# AAA_third_source.net
KiCad netlist of a schematic drawn in EAGLE
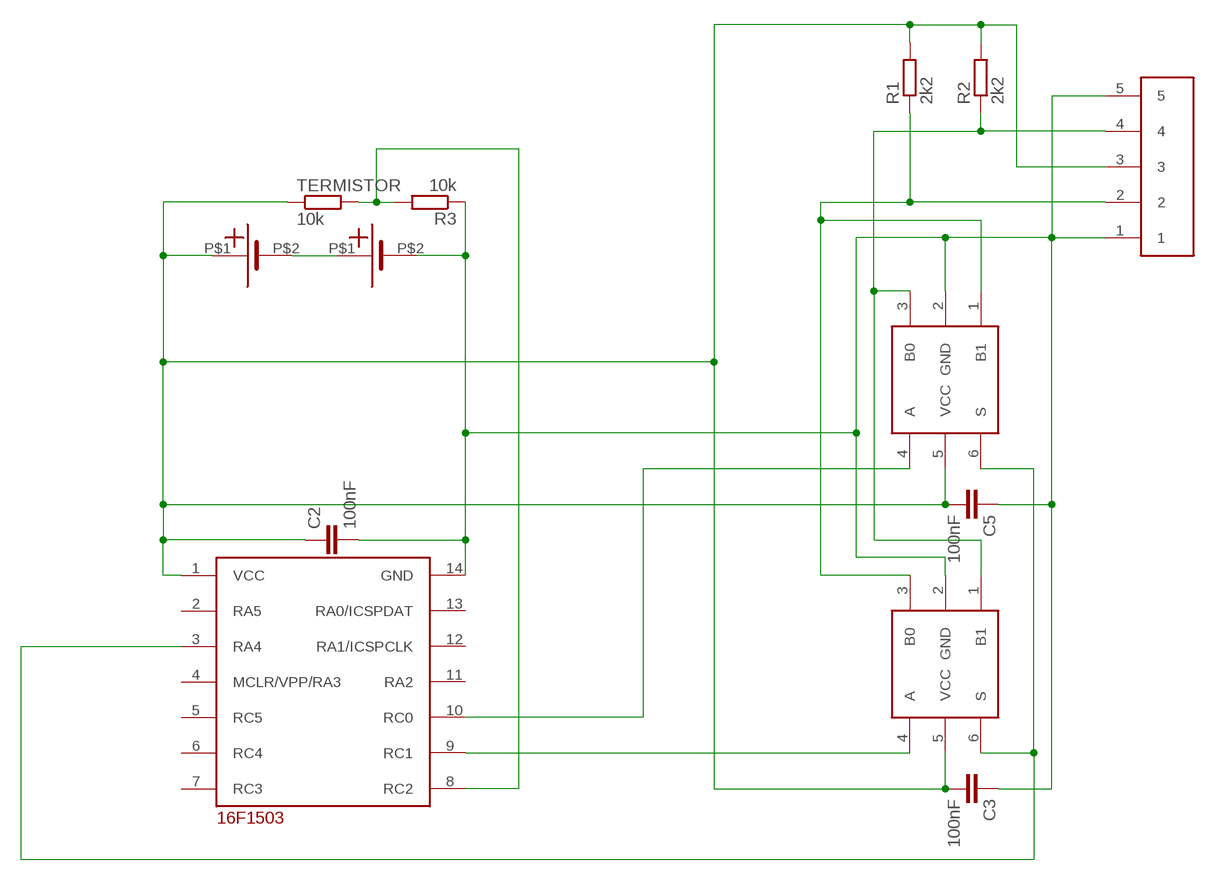
[diagram p0: schematic, sheet 1]

(export (version "E")
  (design (tool "Eeschema 10.0.6"))
  (components
    (comp (ref "C2")
      (value "100nF")
      (footprint "eagle-import:C0603")
      (libsource (lib "eagle-import") (part "C-EUC0603"))
    )
    (comp (ref "C3")
      (value "100nF")
      (footprint "eagle-import:C0603")
      (libsource (lib "eagle-import") (part "C-EUC0603"))
    )
    (comp (ref "C5")
      (value "100nF")
      (footprint "eagle-import:C0603")
      (libsource (lib "eagle-import") (part "C-EUC0603"))
    )
    (comp (ref "R1")
      (value "2k2")
      (footprint "eagle-import:R0603")
      (libsource (lib "eagle-import") (part "R-EU_R0603"))
    )
    (comp (ref "R2")
      (value "2k2")
      (footprint "eagle-import:R0603")
      (libsource (lib "eagle-import") (part "R-EU_R0603"))
    )
    (comp (ref "R3")
      (value "10k")
      (footprint "eagle-import:R0603")
      (libsource (lib "eagle-import") (part "R-EU_R0603"))
    )
    (comp (ref "TERMISTOR")
      (value "10k")
      (footprint "eagle-import:R0603")
      (libsource (lib "eagle-import") (part "R-EU_R0603"))
    )
    (comp (ref "U$1")
      (value "16F103-TSSOP")
      (footprint "eagle-import:TSSOP14")
      (libsource (lib "eagle-import") (part "16F103-TSSOP"))
    )
    (comp (ref "U$2")
      (value "AAA_THIRD")
      (footprint "eagle-import:AAA_THIRD")
      (libsource (lib "eagle-import") (part "AAA_THIRD"))
    )
    (comp (ref "U$3")
      (value "AAA_THIRD")
      (footprint "eagle-import:AAA_THIRD")
      (libsource (lib "eagle-import") (part "AAA_THIRD"))
    )
    (comp (ref "U$5")
      (value "JUMPER5F-90")
      (footprint "eagle-import:JUMPER5F-90")
      (libsource (lib "eagle-import") (part "JUMPER5F-90"))
    )
    (comp (ref "U$6")
      (value "NC7SB3157P6X")
      (footprint "eagle-import:SC70-6L")
      (libsource (lib "eagle-import") (part "NC7SB3157P6X"))
    )
    (comp (ref "U$7")
      (value "NC7SB3157P6X")
      (footprint "eagle-import:SC70-6L")
      (libsource (lib "eagle-import") (part "NC7SB3157P6X"))
    )
  )
  (nets
    (net (code "1") (name "Net-(U$1-GND)") (class "Default")
      (node (ref "C2") (pin "2") (pinfunction "2_2") (pintype "passive"))
      (node (ref "C3") (pin "1") (pinfunction "1_1") (pintype "passive"))
      (node (ref "C5") (pin "1") (pinfunction "1_1") (pintype "passive"))
      (node (ref "R3") (pin "1") (pinfunction "1_1") (pintype "passive"))
      (node (ref "U$1") (pin "14") (pinfunction "GND_14") (pintype "power_in"))
      (node (ref "U$3") (pin "P$2") (pinfunction "$2_P$2") (pintype "power_in"))
      (node (ref "U$5") (pin "1") (pinfunction "1_1") (pintype "bidirectional"))
      (node (ref "U$5") (pin "5") (pinfunction "5_5") (pintype "bidirectional"))
      (node (ref "U$6") (pin "2") (pinfunction "GND_2") (pintype "power_in"))
      (node (ref "U$7") (pin "2") (pinfunction "GND_2") (pintype "power_in"))
    )
    (net (code "2") (name "Net-(U$1-RA4)") (class "Default")
      (node (ref "U$1") (pin "3") (pinfunction "RA4_3") (pintype "bidirectional"))
      (node (ref "U$6") (pin "6") (pinfunction "S_6") (pintype "bidirectional"))
      (node (ref "U$7") (pin "6") (pinfunction "S_6") (pintype "bidirectional"))
    )
    (net (code "3") (name "Net-(U$1-RC0)") (class "Default")
      (node (ref "U$1") (pin "10") (pinfunction "RC0_10") (pintype "bidirectional"))
      (node (ref "U$6") (pin "4") (pinfunction "A_4") (pintype "bidirectional"))
    )
    (net (code "4") (name "Net-(U$1-RC1)") (class "Default")
      (node (ref "U$1") (pin "9") (pinfunction "RC1_9") (pintype "bidirectional"))
      (node (ref "U$7") (pin "4") (pinfunction "A_4") (pintype "bidirectional"))
    )
    (net (code "5") (name "Net-(U$1-RC2)") (class "Default")
      (node (ref "R3") (pin "2") (pinfunction "2_2") (pintype "passive"))
      (node (ref "TERMISTOR") (pin "2") (pinfunction "2_2") (pintype "passive"))
      (node (ref "U$1") (pin "8") (pinfunction "RC2_8") (pintype "bidirectional"))
    )
    (net (code "6") (name "Net-(U$1-VCC)") (class "Default")
      (node (ref "C2") (pin "1") (pinfunction "1_1") (pintype "passive"))
      (node (ref "C3") (pin "2") (pinfunction "2_2") (pintype "passive"))
      (node (ref "C5") (pin "2") (pinfunction "2_2") (pintype "passive"))
      (node (ref "R1") (pin "2") (pinfunction "2_2") (pintype "passive"))
      (node (ref "R2") (pin "2") (pinfunction "2_2") (pintype "passive"))
      (node (ref "TERMISTOR") (pin "1") (pinfunction "1_1") (pintype "passive"))
      (node (ref "U$1") (pin "1") (pinfunction "VCC_1") (pintype "power_in"))
      (node (ref "U$2") (pin "P$1") (pinfunction "$1_P$1") (pintype "power_in"))
      (node (ref "U$5") (pin "3") (pinfunction "3_3") (pintype "bidirectional"))
      (node (ref "U$6") (pin "5") (pinfunction "VCC_5") (pintype "power_in"))
      (node (ref "U$7") (pin "5") (pinfunction "VCC_5") (pintype "power_in"))
    )
    (net (code "7") (name "Net-(U$2-$2)") (class "Default")
      (node (ref "U$2") (pin "P$2") (pinfunction "$2_P$2") (pintype "power_in"))
      (node (ref "U$3") (pin "P$1") (pinfunction "$1_P$1") (pintype "power_in"))
    )
    (net (code "8") (name "Net-(U$6-B0)") (class "Default")
      (node (ref "R2") (pin "1") (pinfunction "1_1") (pintype "passive"))
      (node (ref "U$5") (pin "4") (pinfunction "4_4") (pintype "bidirectional"))
      (node (ref "U$6") (pin "3") (pinfunction "B0_3") (pintype "bidirectional"))
      (node (ref "U$7") (pin "1") (pinfunction "B1_1") (pintype "bidirectional"))
    )
    (net (code "9") (name "Net-(U$6-B1)") (class "Default")
      (node (ref "R1") (pin "1") (pinfunction "1_1") (pintype "passive"))
      (node (ref "U$5") (pin "2") (pinfunction "2_2") (pintype "bidirectional"))
      (node (ref "U$6") (pin "1") (pinfunction "B1_1") (pintype "bidirectional"))
      (node (ref "U$7") (pin "3") (pinfunction "B0_3") (pintype "bidirectional"))
    )
    (net (code "10") (name "unconnected-(U$1-MCLR{slash}VPP{slash}RA3-Pad4)") (class "Default")
      (node (ref "U$1") (pin "4") (pinfunction "MCLR/VPP/RA3_4") (pintype "bidirectional"))
    )
    (net (code "11") (name "unconnected-(U$1-RA0{slash}ICSPDAT-Pad13)") (class "Default")
      (node (ref "U$1") (pin "13") (pinfunction "RA0/ICSPDAT_13") (pintype "bidirectional"))
    )
    (net (code "12") (name "unconnected-(U$1-RA1{slash}ICSPCLK-Pad12)") (class "Default")
      (node (ref "U$1") (pin "12") (pinfunction "RA1/ICSPCLK_12") (pintype "bidirectional"))
    )
    (net (code "13") (name "unconnected-(U$1-RA2-Pad11)") (class "Default")
      (node (ref "U$1") (pin "11") (pinfunction "RA2_11") (pintype "bidirectional"))
    )
    (net (code "14") (name "unconnected-(U$1-RA5-Pad2)") (class "Default")
      (node (ref "U$1") (pin "2") (pinfunction "RA5_2") (pintype "bidirectional"))
    )
    (net (code "15") (name "unconnected-(U$1-RC3-Pad7)") (class "Default")
      (node (ref "U$1") (pin "7") (pinfunction "RC3_7") (pintype "bidirectional"))
    )
    (net (code "16") (name "unconnected-(U$1-RC4-Pad6)") (class "Default")
      (node (ref "U$1") (pin "6") (pinfunction "RC4_6") (pintype "bidirectional"))
    )
    (net (code "17") (name "unconnected-(U$1-RC5-Pad5)") (class "Default")
      (node (ref "U$1") (pin "5") (pinfunction "RC5_5") (pintype "bidirectional"))
    )
  )
)
